# power-shield-v220.net
KiCad netlist of a schematic drawn in EAGLE
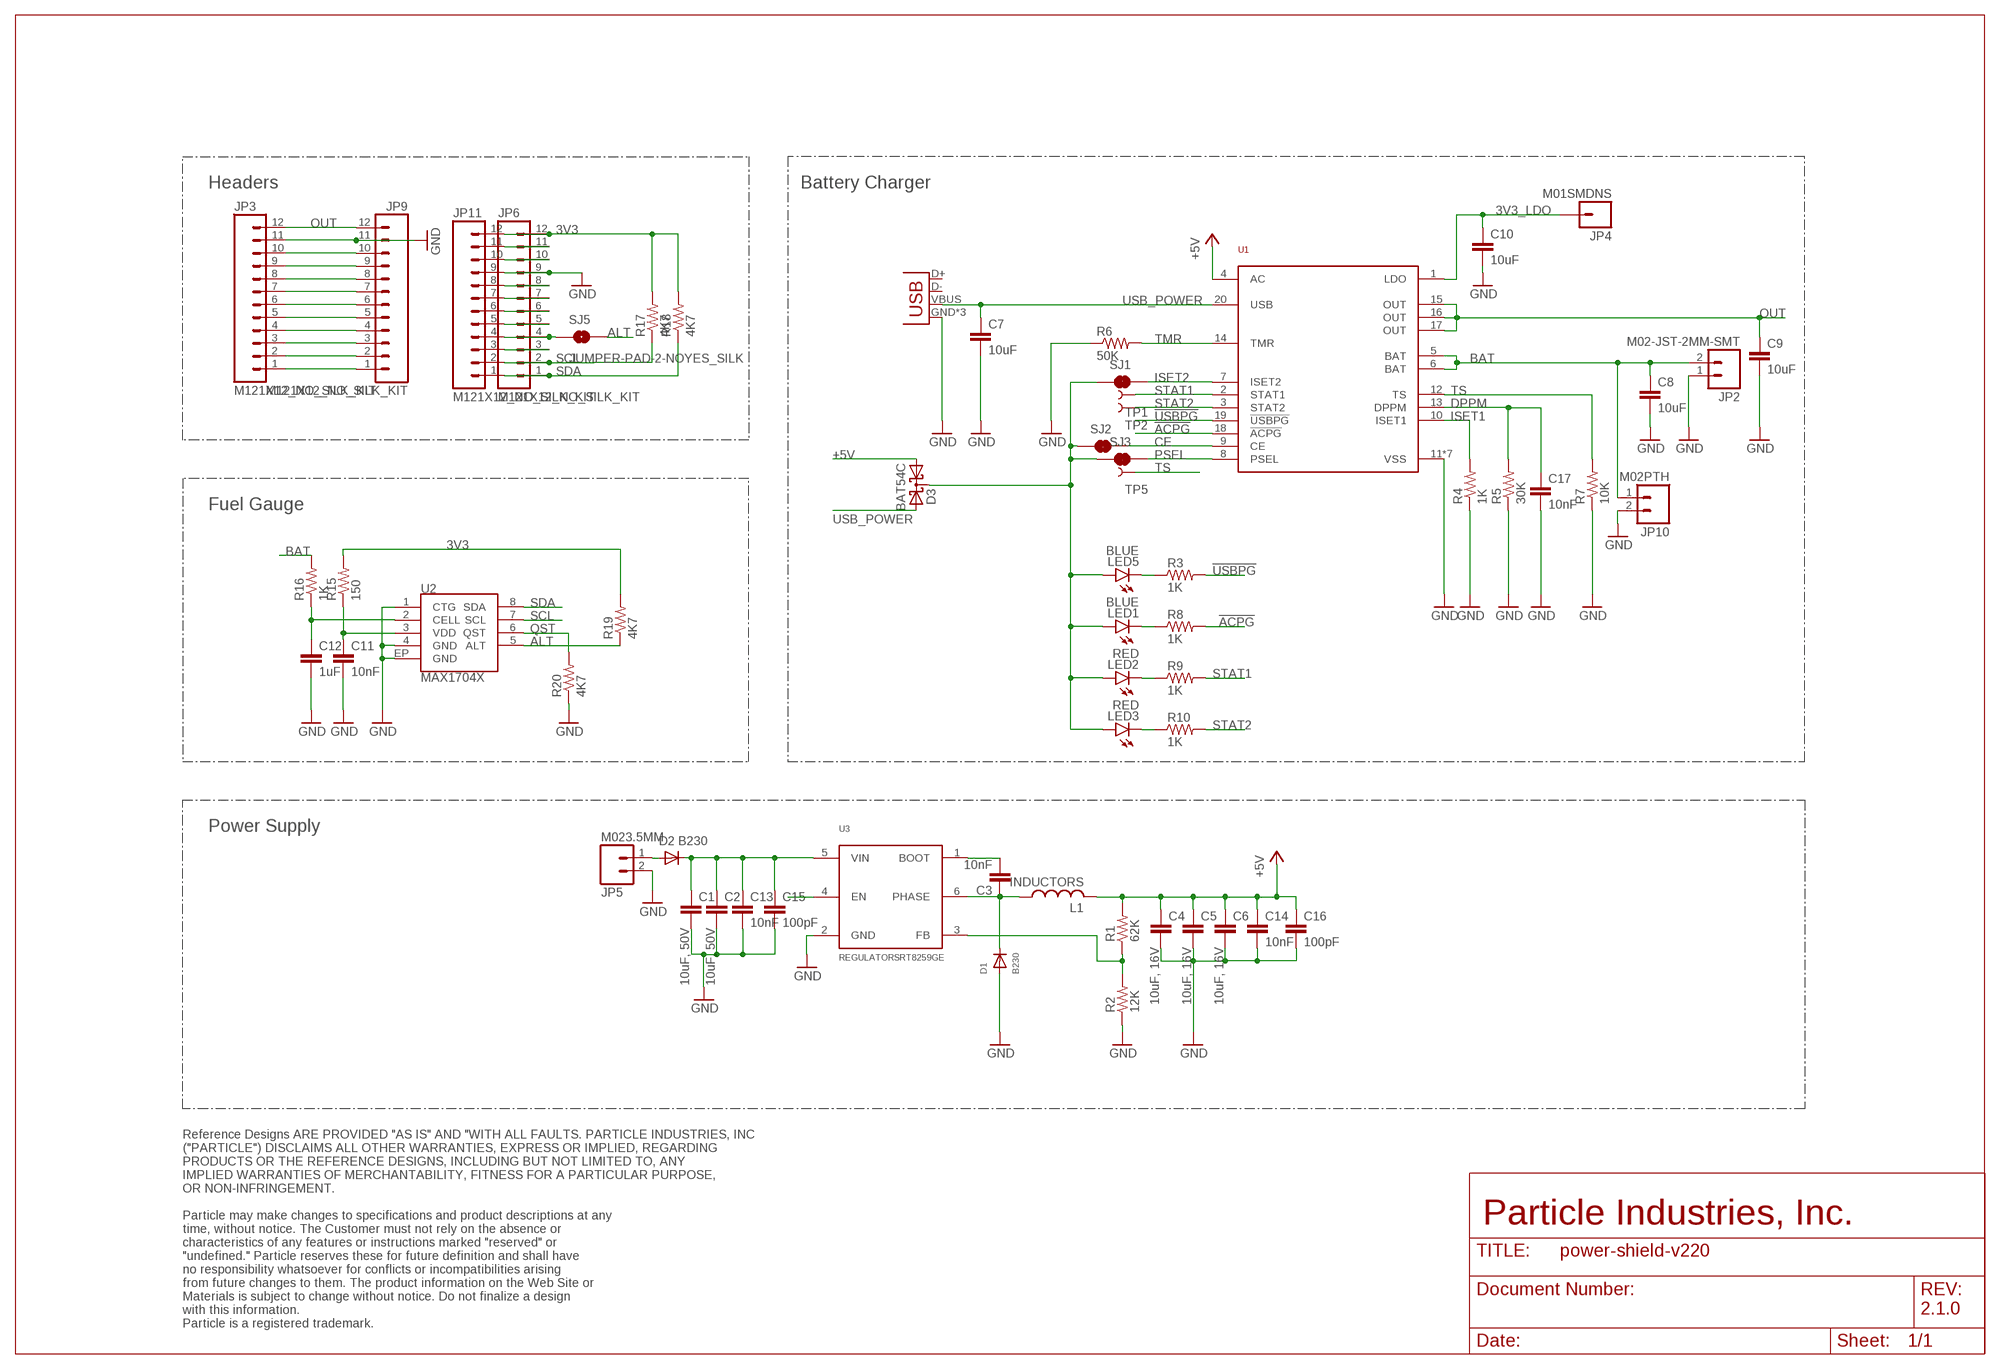
[diagram p0: schematic, sheet 1]

(export (version "E")
  (design (tool "Eeschema 10.0.6"))
  (components
    (comp (ref "C1")
      (value "10uF, 50V")
      (footprint "eagle-import:1206")
      (libsource (lib "eagle-import") (part "CAP1206"))
    )
    (comp (ref "C2")
      (value "10uF, 50V")
      (footprint "eagle-import:1206")
      (libsource (lib "eagle-import") (part "CAP1206"))
    )
    (comp (ref "C3")
      (value "10nF")
      (footprint "eagle-import:0402-CAP")
      (libsource (lib "eagle-import") (part "CAP0402-CAP"))
    )
    (comp (ref "C4")
      (value "10uF, 16V")
      (footprint "eagle-import:1206")
      (libsource (lib "eagle-import") (part "CAP1206"))
    )
    (comp (ref "C5")
      (value "10uF, 16V")
      (footprint "eagle-import:1206")
      (libsource (lib "eagle-import") (part "CAP1206"))
    )
    (comp (ref "C6")
      (value "10uF, 16V")
      (footprint "eagle-import:1206")
      (libsource (lib "eagle-import") (part "CAP1206"))
    )
    (comp (ref "C7")
      (value "10uF")
      (footprint "eagle-import:0603-CAP")
      (libsource (lib "eagle-import") (part "CAP0603-CAP"))
    )
    (comp (ref "C8")
      (value "10uF")
      (footprint "eagle-import:0603-CAP")
      (libsource (lib "eagle-import") (part "CAP0603-CAP"))
    )
    (comp (ref "C9")
      (value "10uF")
      (footprint "eagle-import:0603-CAP")
      (libsource (lib "eagle-import") (part "CAP0603-CAP"))
    )
    (comp (ref "C10")
      (value "10uF")
      (footprint "eagle-import:0603-CAP")
      (libsource (lib "eagle-import") (part "CAP0603-CAP"))
    )
    (comp (ref "C11")
      (value "10nF")
      (footprint "eagle-import:0402-CAP")
      (libsource (lib "eagle-import") (part "CAP0402-CAP"))
    )
    (comp (ref "C12")
      (value "1uF")
      (footprint "eagle-import:0402-CAP")
      (libsource (lib "eagle-import") (part "CAP0402-CAP"))
    )
    (comp (ref "C13")
      (value "10nF")
      (footprint "eagle-import:0402-CAP")
      (libsource (lib "eagle-import") (part "CAP0402-CAP"))
    )
    (comp (ref "C14")
      (value "10nF")
      (footprint "eagle-import:0402-CAP")
      (libsource (lib "eagle-import") (part "CAP0402-CAP"))
    )
    (comp (ref "C15")
      (value "100pF")
      (footprint "eagle-import:0402-CAP")
      (libsource (lib "eagle-import") (part "CAP0402-CAP"))
    )
    (comp (ref "C16")
      (value "100pF")
      (footprint "eagle-import:0402-CAP")
      (libsource (lib "eagle-import") (part "CAP0402-CAP"))
    )
    (comp (ref "C17")
      (value "10nF")
      (footprint "eagle-import:0402-CAP")
      (libsource (lib "eagle-import") (part "CAP0402-CAP"))
    )
    (comp (ref "D1")
      (value "B230")
      (footprint "eagle-import:SMADIODE")
      (libsource (lib "eagle-import") (part "DIODESMA"))
    )
    (comp (ref "D2")
      (value "B230")
      (footprint "eagle-import:SMADIODE")
      (libsource (lib "eagle-import") (part "DIODESMA"))
    )
    (comp (ref "D3")
      (value "BAT54C")
      (footprint "eagle-import:SOT23")
      (libsource (lib "eagle-import") (part "BAT54C"))
    )
    (comp (ref "JP1")
      (value "USBUSB-MICROB-SLOT-HOLE")
      (footprint "eagle-import:USB-MICROB-SLOT-HOLE")
      (libsource (lib "eagle-import") (part "USBUSB-MICROB-SLOT-HOLE"))
    )
    (comp (ref "JP2")
      (value "M02-JST-2MM-SMT")
      (footprint "eagle-import:JST-2-SMD")
      (libsource (lib "eagle-import") (part "M02-JST-2MM-SMT"))
    )
    (comp (ref "JP3")
      (value "M121X12_NO_SILK_KIT")
      (footprint "eagle-import:1X12_NO_SILK_KIT")
      (libsource (lib "eagle-import") (part "M121X12_NO_SILK_KIT"))
    )
    (comp (ref "JP4")
      (value "M01SMDNS")
      (footprint "eagle-import:1X01NS")
      (libsource (lib "eagle-import") (part "M01SMDNS"))
    )
    (comp (ref "JP5")
      (value "M023.5MM")
      (footprint "eagle-import:SCREWTERMINAL-3.5MM-2")
      (libsource (lib "eagle-import") (part "M023.5MM"))
    )
    (comp (ref "JP6")
      (value "M121X12_NO_SILK_KIT")
      (footprint "eagle-import:1X12_NO_SILK_KIT")
      (libsource (lib "eagle-import") (part "M121X12_NO_SILK_KIT"))
    )
    (comp (ref "JP9")
      (value "M121X12_NO_SILK_KIT")
      (footprint "eagle-import:1X12_NO_SILK_KIT")
      (libsource (lib "eagle-import") (part "M121X12_NO_SILK_KIT"))
    )
    (comp (ref "JP10")
      (value "M02PTH")
      (footprint "eagle-import:1X02")
      (libsource (lib "eagle-import") (part "M02PTH"))
    )
    (comp (ref "JP11")
      (value "M121X12_NO_SILK_KIT")
      (footprint "eagle-import:1X12_NO_SILK_KIT")
      (libsource (lib "eagle-import") (part "M121X12_NO_SILK_KIT"))
    )
    (comp (ref "L1")
      (value "INDUCTORS")
      (footprint "eagle-import:NR8040T6R8N")
      (libsource (lib "eagle-import") (part "INDUCTORS"))
    )
    (comp (ref "LED1")
      (value "BLUE")
      (footprint "eagle-import:LED-0603")
      (libsource (lib "eagle-import") (part "LED0603"))
    )
    (comp (ref "LED2")
      (value "RED")
      (footprint "eagle-import:LED-0603")
      (libsource (lib "eagle-import") (part "LED0603"))
    )
    (comp (ref "LED3")
      (value "RED")
      (footprint "eagle-import:LED-0603")
      (libsource (lib "eagle-import") (part "LED0603"))
    )
    (comp (ref "LED5")
      (value "BLUE")
      (footprint "eagle-import:LED-0603")
      (libsource (lib "eagle-import") (part "LED0603"))
    )
    (comp (ref "R1")
      (value "62K")
      (footprint "eagle-import:0603-RES")
      (libsource (lib "eagle-import") (part "RESISTOR0603-RES"))
    )
    (comp (ref "R2")
      (value "12K")
      (footprint "eagle-import:0603-RES")
      (libsource (lib "eagle-import") (part "RESISTOR0603-RES"))
    )
    (comp (ref "R3")
      (value "1K")
      (footprint "eagle-import:0402-RES")
      (libsource (lib "eagle-import") (part "RESISTOR0402-RES"))
    )
    (comp (ref "R4")
      (value "1K")
      (footprint "eagle-import:0402-RES")
      (libsource (lib "eagle-import") (part "RESISTOR0402-RES"))
    )
    (comp (ref "R5")
      (value "30K")
      (footprint "eagle-import:0402-RES")
      (libsource (lib "eagle-import") (part "RESISTOR0402-RES"))
    )
    (comp (ref "R6")
      (value "50K")
      (footprint "eagle-import:0402-RES")
      (libsource (lib "eagle-import") (part "RESISTOR0402-RES"))
    )
    (comp (ref "R7")
      (value "10K")
      (footprint "eagle-import:0402-RES")
      (libsource (lib "eagle-import") (part "RESISTOR0402-RES"))
    )
    (comp (ref "R8")
      (value "1K")
      (footprint "eagle-import:0402-RES")
      (libsource (lib "eagle-import") (part "RESISTOR0402-RES"))
    )
    (comp (ref "R9")
      (value "1K")
      (footprint "eagle-import:0402-RES")
      (libsource (lib "eagle-import") (part "RESISTOR0402-RES"))
    )
    (comp (ref "R10")
      (value "1K")
      (footprint "eagle-import:0402-RES")
      (libsource (lib "eagle-import") (part "RESISTOR0402-RES"))
    )
    (comp (ref "R15")
      (value "150")
      (footprint "eagle-import:0603-RES")
      (libsource (lib "eagle-import") (part "RESISTOR0603-RES"))
    )
    (comp (ref "R16")
      (value "1K")
      (footprint "eagle-import:0603-RES")
      (libsource (lib "eagle-import") (part "RESISTOR0603-RES"))
    )
    (comp (ref "R17")
      (value "4K7")
      (footprint "eagle-import:0402-RES")
      (libsource (lib "eagle-import") (part "RESISTOR0402-RES"))
    )
    (comp (ref "R18")
      (value "4K7")
      (footprint "eagle-import:0402-RES")
      (libsource (lib "eagle-import") (part "RESISTOR0402-RES"))
    )
    (comp (ref "R19")
      (value "4K7")
      (footprint "eagle-import:0402-RES")
      (libsource (lib "eagle-import") (part "RESISTOR0402-RES"))
    )
    (comp (ref "R20")
      (value "4K7")
      (footprint "eagle-import:0402-RES")
      (libsource (lib "eagle-import") (part "RESISTOR0402-RES"))
    )
    (comp (ref "SJ1")
      (value "JUMPER-PAD-2-NC_BY_TRACE")
      (footprint "eagle-import:PAD-JUMPER-2-NC_BY_TRACE_YES_SILK")
      (libsource (lib "eagle-import") (part "JUMPER-PAD-2-NC_BY_TRACE"))
    )
    (comp (ref "SJ2")
      (value "JUMPER-PAD-2-NC_BY_TRACE")
      (footprint "eagle-import:PAD-JUMPER-2-NC_BY_TRACE_YES_SILK")
      (libsource (lib "eagle-import") (part "JUMPER-PAD-2-NC_BY_TRACE"))
    )
    (comp (ref "SJ3")
      (value "JUMPER-PAD-2-NC_BY_TRACE")
      (footprint "eagle-import:PAD-JUMPER-2-NC_BY_TRACE_YES_SILK")
      (libsource (lib "eagle-import") (part "JUMPER-PAD-2-NC_BY_TRACE"))
    )
    (comp (ref "SJ5")
      (value "JUMPER-PAD-2-NOYES_SILK")
      (footprint "eagle-import:PAD-JUMPER-2-NO_YES_SILK")
      (libsource (lib "eagle-import") (part "JUMPER-PAD-2-NOYES_SILK"))
    )
    (comp (ref "TP1")
      (value "TEST-POINT3")
      (footprint "eagle-import:PAD.03X.03")
      (libsource (lib "eagle-import") (part "TEST-POINT3"))
    )
    (comp (ref "TP2")
      (value "TEST-POINT3")
      (footprint "eagle-import:PAD.03X.03")
      (libsource (lib "eagle-import") (part "TEST-POINT3"))
    )
    (comp (ref "TP5")
      (value "TEST-POINT3")
      (footprint "eagle-import:PAD.03X.03")
      (libsource (lib "eagle-import") (part "TEST-POINT3"))
    )
    (comp (ref "U1")
      (value "BQ24030BQ24030")
      (footprint "eagle-import:R-PVQFN-N20")
      (libsource (lib "eagle-import") (part "BQ24030BQ24030"))
    )
    (comp (ref "U2")
      (value "MAX1704X")
      (footprint "eagle-import:TDFN-8")
      (libsource (lib "eagle-import") (part "MAX1704X"))
    )
    (comp (ref "U3")
      (value "REGULATORSRT8259GE")
      (footprint "eagle-import:SOT23-6")
      (libsource (lib "eagle-import") (part "REGULATORSRT8259GE"))
    )
  )
  (nets
    (net (code "1") (name "+5V") (class "Default")
      (node (ref "C14") (pin "1") (pinfunction "1_1") (pintype "passive"))
      (node (ref "C16") (pin "1") (pinfunction "1_1") (pintype "passive"))
      (node (ref "C4") (pin "1") (pinfunction "1_1") (pintype "passive"))
      (node (ref "C5") (pin "1") (pinfunction "1_1") (pintype "passive"))
      (node (ref "C6") (pin "1") (pinfunction "1_1") (pintype "passive"))
      (node (ref "D3") (pin "1") (pinfunction "A1_1") (pintype "passive"))
      (node (ref "L1") (pin "P$2") (pinfunction "2_P$2") (pintype "passive"))
      (node (ref "R1") (pin "2") (pinfunction "2_2") (pintype "passive"))
      (node (ref "U1") (pin "4") (pinfunction "AC_4") (pintype "power_in"))
    )
    (net (code "2") (name "/3V3") (class "Default")
      (node (ref "JP11") (pin "12") (pinfunction "12_12") (pintype "passive"))
      (node (ref "JP6") (pin "12") (pinfunction "12_12") (pintype "passive"))
      (node (ref "R15") (pin "2") (pinfunction "2_2") (pintype "passive"))
      (node (ref "R17") (pin "2") (pinfunction "2_2") (pintype "passive"))
      (node (ref "R18") (pin "2") (pinfunction "2_2") (pintype "passive"))
      (node (ref "R19") (pin "2") (pinfunction "2_2") (pintype "passive"))
    )
    (net (code "3") (name "/3V3_LDO") (class "Default")
      (node (ref "C10") (pin "1") (pinfunction "1_1") (pintype "passive"))
      (node (ref "JP4") (pin "1") (pinfunction "1_1") (pintype "passive"))
      (node (ref "U1") (pin "1") (pinfunction "LDO_1") (pintype "output"))
    )
    (net (code "4") (name "/ALT") (class "Default")
      (node (ref "R19") (pin "1") (pinfunction "1_1") (pintype "passive"))
      (node (ref "SJ5") (pin "2") (pinfunction "2_2") (pintype "passive"))
      (node (ref "U2") (pin "5") (pinfunction "ALT_5") (pintype "bidirectional"))
    )
    (net (code "5") (name "/BAT") (class "Default")
      (node (ref "C8") (pin "1") (pinfunction "1_1") (pintype "passive"))
      (node (ref "JP10") (pin "1") (pinfunction "1_1") (pintype "passive"))
      (node (ref "JP2") (pin "2") (pinfunction "1_2") (pintype "passive"))
      (node (ref "R16") (pin "2") (pinfunction "2_2") (pintype "passive"))
      (node (ref "U1") (pin "5") (pinfunction "BAT_5") (pintype "output"))
      (node (ref "U1") (pin "6") (pinfunction "BAT_6") (pintype "output"))
    )
    (net (code "6") (name "/CE") (class "Default")
      (node (ref "SJ2") (pin "2") (pinfunction "2_2") (pintype "passive"))
      (node (ref "U1") (pin "9") (pinfunction "CE_9") (pintype "input"))
    )
    (net (code "7") (name "/DPPM") (class "Default")
      (node (ref "C17") (pin "1") (pinfunction "1_1") (pintype "passive"))
      (node (ref "R5") (pin "2") (pinfunction "2_2") (pintype "passive"))
      (node (ref "U1") (pin "13") (pinfunction "DPPM_13") (pintype "bidirectional"))
    )
    (net (code "8") (name "/ISET1") (class "Default")
      (node (ref "R4") (pin "2") (pinfunction "2_2") (pintype "passive"))
      (node (ref "U1") (pin "10") (pinfunction "ISET1_10") (pintype "bidirectional"))
    )
    (net (code "9") (name "/ISET2") (class "Default")
      (node (ref "SJ1") (pin "2") (pinfunction "2_2") (pintype "passive"))
      (node (ref "U1") (pin "7") (pinfunction "ISET2_7") (pintype "input"))
    )
    (net (code "10") (name "/OUT") (class "Default")
      (node (ref "C9") (pin "1") (pinfunction "1_1") (pintype "passive"))
      (node (ref "JP3") (pin "12") (pinfunction "12_12") (pintype "passive"))
      (node (ref "JP9") (pin "12") (pinfunction "12_12") (pintype "passive"))
      (node (ref "U1") (pin "15") (pinfunction "OUT_15") (pintype "output"))
      (node (ref "U1") (pin "16") (pinfunction "OUT_16") (pintype "output"))
      (node (ref "U1") (pin "17") (pinfunction "OUT_17") (pintype "output"))
    )
    (net (code "11") (name "/PSEL") (class "Default")
      (node (ref "SJ3") (pin "2") (pinfunction "2_2") (pintype "passive"))
      (node (ref "U1") (pin "8") (pinfunction "PSEL_8") (pintype "input"))
    )
    (net (code "12") (name "/QST") (class "Default")
      (node (ref "R20") (pin "2") (pinfunction "2_2") (pintype "passive"))
      (node (ref "U2") (pin "6") (pinfunction "QST_6") (pintype "bidirectional"))
    )
    (net (code "13") (name "/SCL") (class "Default")
      (node (ref "JP11") (pin "2") (pinfunction "2_2") (pintype "passive"))
      (node (ref "JP6") (pin "2") (pinfunction "2_2") (pintype "passive"))
      (node (ref "R17") (pin "1") (pinfunction "1_1") (pintype "passive"))
      (node (ref "U2") (pin "7") (pinfunction "SCL_7") (pintype "bidirectional"))
    )
    (net (code "14") (name "/SDA") (class "Default")
      (node (ref "JP11") (pin "1") (pinfunction "1_1") (pintype "passive"))
      (node (ref "JP6") (pin "1") (pinfunction "1_1") (pintype "passive"))
      (node (ref "R18") (pin "1") (pinfunction "1_1") (pintype "passive"))
      (node (ref "U2") (pin "8") (pinfunction "SDA_8") (pintype "bidirectional"))
    )
    (net (code "15") (name "/STAT1") (class "Default")
      (node (ref "R9") (pin "2") (pinfunction "2_2") (pintype "passive"))
      (node (ref "TP1") (pin "P$1") (pinfunction "1_P$1") (pintype "bidirectional"))
      (node (ref "U1") (pin "2") (pinfunction "STAT1_2") (pintype "output"))
    )
    (net (code "16") (name "/STAT2") (class "Default")
      (node (ref "R10") (pin "2") (pinfunction "2_2") (pintype "passive"))
      (node (ref "TP2") (pin "P$1") (pinfunction "1_P$1") (pintype "bidirectional"))
      (node (ref "U1") (pin "3") (pinfunction "STAT2_3") (pintype "output"))
    )
    (net (code "17") (name "/TMR") (class "Default")
      (node (ref "R6") (pin "2") (pinfunction "2_2") (pintype "passive"))
      (node (ref "U1") (pin "14") (pinfunction "TMR_14") (pintype "power_in"))
    )
    (net (code "18") (name "/TS") (class "Default")
      (node (ref "R7") (pin "2") (pinfunction "2_2") (pintype "passive"))
      (node (ref "TP5") (pin "P$1") (pinfunction "1_P$1") (pintype "bidirectional"))
      (node (ref "U1") (pin "12") (pinfunction "TS_12") (pintype "bidirectional"))
    )
    (net (code "19") (name "/USB_POWER") (class "Default")
      (node (ref "C7") (pin "1") (pinfunction "1_1") (pintype "passive"))
      (node (ref "D3") (pin "2") (pinfunction "A2_2") (pintype "passive"))
      (node (ref "JP1") (pin "VBUS") (pinfunction "VBUS_VBUS") (pintype "bidirectional"))
      (node (ref "U1") (pin "20") (pinfunction "USB_20") (pintype "power_in"))
    )
    (net (code "20") (name "/~{ACPG}") (class "Default")
      (node (ref "R8") (pin "2") (pinfunction "2_2") (pintype "passive"))
      (node (ref "U1") (pin "18") (pinfunction "~{ACPG}_18") (pintype "input"))
    )
    (net (code "21") (name "/~{USBPG}") (class "Default")
      (node (ref "R3") (pin "2") (pinfunction "2_2") (pintype "passive"))
      (node (ref "U1") (pin "19") (pinfunction "~{USBPG}_19") (pintype "input"))
    )
    (net (code "22") (name "GND") (class "Default")
      (node (ref "C1") (pin "2") (pinfunction "2_2") (pintype "passive"))
      (node (ref "C10") (pin "2") (pinfunction "2_2") (pintype "passive"))
      (node (ref "C11") (pin "2") (pinfunction "2_2") (pintype "passive"))
      (node (ref "C12") (pin "2") (pinfunction "2_2") (pintype "passive"))
      (node (ref "C13") (pin "2") (pinfunction "2_2") (pintype "passive"))
      (node (ref "C14") (pin "2") (pinfunction "2_2") (pintype "passive"))
      (node (ref "C15") (pin "2") (pinfunction "2_2") (pintype "passive"))
      (node (ref "C16") (pin "2") (pinfunction "2_2") (pintype "passive"))
      (node (ref "C17") (pin "2") (pinfunction "2_2") (pintype "passive"))
      (node (ref "C2") (pin "2") (pinfunction "2_2") (pintype "passive"))
      (node (ref "C4") (pin "2") (pinfunction "2_2") (pintype "passive"))
      (node (ref "C5") (pin "2") (pinfunction "2_2") (pintype "passive"))
      (node (ref "C6") (pin "2") (pinfunction "2_2") (pintype "passive"))
      (node (ref "C7") (pin "2") (pinfunction "2_2") (pintype "passive"))
      (node (ref "C8") (pin "2") (pinfunction "2_2") (pintype "passive"))
      (node (ref "C9") (pin "2") (pinfunction "2_2") (pintype "passive"))
      (node (ref "D1") (pin "A") (pinfunction "A_A") (pintype "passive"))
      (node (ref "JP1") (pin "GND") (pinfunction "GND_GND") (pintype "bidirectional"))
      (node (ref "JP1") (pin "MT1") (pinfunction "GND_MT1") (pintype "bidirectional"))
      (node (ref "JP1") (pin "MT2") (pinfunction "GND_MT2") (pintype "bidirectional"))
      (node (ref "JP10") (pin "2") (pinfunction "2_2") (pintype "passive"))
      (node (ref "JP11") (pin "9") (pinfunction "9_9") (pintype "passive"))
      (node (ref "JP2") (pin "1") (pinfunction "2_1") (pintype "passive"))
      (node (ref "JP3") (pin "11") (pinfunction "11_11") (pintype "passive"))
      (node (ref "JP5") (pin "2") (pinfunction "2_2") (pintype "passive"))
      (node (ref "JP6") (pin "9") (pinfunction "9_9") (pintype "passive"))
      (node (ref "JP9") (pin "11") (pinfunction "11_11") (pintype "passive"))
      (node (ref "R2") (pin "1") (pinfunction "1_1") (pintype "passive"))
      (node (ref "R20") (pin "1") (pinfunction "1_1") (pintype "passive"))
      (node (ref "R4") (pin "1") (pinfunction "1_1") (pintype "passive"))
      (node (ref "R5") (pin "1") (pinfunction "1_1") (pintype "passive"))
      (node (ref "R6") (pin "1") (pinfunction "1_1") (pintype "passive"))
      (node (ref "R7") (pin "1") (pinfunction "1_1") (pintype "passive"))
      (node (ref "U1") (pin "11") (pinfunction "VSS_11") (pintype "power_in"))
      (node (ref "U1") (pin "21") (pinfunction "VSS_21") (pintype "power_in"))
      (node (ref "U1") (pin "22") (pinfunction "VSS_22") (pintype "power_in"))
      (node (ref "U1") (pin "23") (pinfunction "VSS_23") (pintype "power_in"))
      (node (ref "U1") (pin "24") (pinfunction "VSS_24") (pintype "power_in"))
      (node (ref "U1") (pin "25") (pinfunction "VSS_25") (pintype "power_in"))
      (node (ref "U1") (pin "26") (pinfunction "VSS_26") (pintype "power_in"))
      (node (ref "U2") (pin "1") (pinfunction "CTG_1") (pintype "bidirectional"))
      (node (ref "U2") (pin "4") (pinfunction "GND_4") (pintype "bidirectional"))
      (node (ref "U2") (pin "EP") (pinfunction "GND_EP") (pintype "bidirectional"))
      (node (ref "U3") (pin "2") (pinfunction "GND_2") (pintype "bidirectional"))
    )
    (net (code "23") (name "Net-(D2-PadA)") (class "Default")
      (node (ref "D2") (pin "A") (pinfunction "A_A") (pintype "passive"))
      (node (ref "JP5") (pin "1") (pinfunction "1_1") (pintype "passive"))
    )
    (net (code "24") (name "Net-(D3-CC)") (class "Default")
      (node (ref "D3") (pin "3") (pinfunction "CC_3") (pintype "passive"))
      (node (ref "LED1") (pin "A") (pinfunction "A_A") (pintype "passive"))
      (node (ref "LED2") (pin "A") (pinfunction "A_A") (pintype "passive"))
      (node (ref "LED3") (pin "A") (pinfunction "A_A") (pintype "passive"))
      (node (ref "LED5") (pin "A") (pinfunction "A_A") (pintype "passive"))
      (node (ref "SJ1") (pin "1") (pinfunction "1_1") (pintype "passive"))
      (node (ref "SJ2") (pin "1") (pinfunction "1_1") (pintype "passive"))
      (node (ref "SJ3") (pin "1") (pinfunction "1_1") (pintype "passive"))
    )
    (net (code "25") (name "Net-(JP3-Pad1)") (class "Default")
      (node (ref "JP3") (pin "1") (pinfunction "1_1") (pintype "passive"))
      (node (ref "JP9") (pin "1") (pinfunction "1_1") (pintype "passive"))
    )
    (net (code "26") (name "Net-(JP3-Pad2)") (class "Default")
      (node (ref "JP3") (pin "2") (pinfunction "2_2") (pintype "passive"))
      (node (ref "JP9") (pin "2") (pinfunction "2_2") (pintype "passive"))
    )
    (net (code "27") (name "Net-(JP3-Pad3)") (class "Default")
      (node (ref "JP3") (pin "3") (pinfunction "3_3") (pintype "passive"))
      (node (ref "JP9") (pin "3") (pinfunction "3_3") (pintype "passive"))
    )
    (net (code "28") (name "Net-(JP3-Pad4)") (class "Default")
      (node (ref "JP3") (pin "4") (pinfunction "4_4") (pintype "passive"))
      (node (ref "JP9") (pin "4") (pinfunction "4_4") (pintype "passive"))
    )
    (net (code "29") (name "Net-(JP3-Pad5)") (class "Default")
      (node (ref "JP3") (pin "5") (pinfunction "5_5") (pintype "passive"))
      (node (ref "JP9") (pin "5") (pinfunction "5_5") (pintype "passive"))
    )
    (net (code "30") (name "Net-(JP3-Pad6)") (class "Default")
      (node (ref "JP3") (pin "6") (pinfunction "6_6") (pintype "passive"))
      (node (ref "JP9") (pin "6") (pinfunction "6_6") (pintype "passive"))
    )
    (net (code "31") (name "Net-(JP3-Pad7)") (class "Default")
      (node (ref "JP3") (pin "7") (pinfunction "7_7") (pintype "passive"))
      (node (ref "JP9") (pin "7") (pinfunction "7_7") (pintype "passive"))
    )
    (net (code "32") (name "Net-(JP3-Pad8)") (class "Default")
      (node (ref "JP3") (pin "8") (pinfunction "8_8") (pintype "passive"))
      (node (ref "JP9") (pin "8") (pinfunction "8_8") (pintype "passive"))
    )
    (net (code "33") (name "Net-(JP3-Pad9)") (class "Default")
      (node (ref "JP3") (pin "9") (pinfunction "9_9") (pintype "passive"))
      (node (ref "JP9") (pin "9") (pinfunction "9_9") (pintype "passive"))
    )
    (net (code "34") (name "Net-(JP3-Pad10)") (class "Default")
      (node (ref "JP3") (pin "10") (pinfunction "10_10") (pintype "passive"))
      (node (ref "JP9") (pin "10") (pinfunction "10_10") (pintype "passive"))
    )
    (net (code "35") (name "Net-(JP11-Pad3)") (class "Default")
      (node (ref "JP11") (pin "3") (pinfunction "3_3") (pintype "passive"))
      (node (ref "JP6") (pin "3") (pinfunction "3_3") (pintype "passive"))
    )
    (net (code "36") (name "Net-(JP11-Pad4)") (class "Default")
      (node (ref "JP11") (pin "4") (pinfunction "4_4") (pintype "passive"))
      (node (ref "JP6") (pin "4") (pinfunction "4_4") (pintype "passive"))
      (node (ref "SJ5") (pin "1") (pinfunction "1_1") (pintype "passive"))
    )
    (net (code "37") (name "Net-(JP11-Pad5)") (class "Default")
      (node (ref "JP11") (pin "5") (pinfunction "5_5") (pintype "passive"))
      (node (ref "JP6") (pin "5") (pinfunction "5_5") (pintype "passive"))
    )
    (net (code "38") (name "Net-(JP11-Pad6)") (class "Default")
      (node (ref "JP11") (pin "6") (pinfunction "6_6") (pintype "passive"))
      (node (ref "JP6") (pin "6") (pinfunction "6_6") (pintype "passive"))
    )
    (net (code "39") (name "Net-(JP11-Pad7)") (class "Default")
      (node (ref "JP11") (pin "7") (pinfunction "7_7") (pintype "passive"))
      (node (ref "JP6") (pin "7") (pinfunction "7_7") (pintype "passive"))
    )
    (net (code "40") (name "Net-(JP11-Pad8)") (class "Default")
      (node (ref "JP11") (pin "8") (pinfunction "8_8") (pintype "passive"))
      (node (ref "JP6") (pin "8") (pinfunction "8_8") (pintype "passive"))
    )
    (net (code "41") (name "Net-(JP11-Pad10)") (class "Default")
      (node (ref "JP11") (pin "10") (pinfunction "10_10") (pintype "passive"))
      (node (ref "JP6") (pin "10") (pinfunction "10_10") (pintype "passive"))
    )
    (net (code "42") (name "Net-(JP11-Pad11)") (class "Default")
      (node (ref "JP11") (pin "11") (pinfunction "11_11") (pintype "passive"))
      (node (ref "JP6") (pin "11") (pinfunction "11_11") (pintype "passive"))
    )
    (net (code "43") (name "Net-(L1-1)") (class "Default")
      (node (ref "C3") (pin "1") (pinfunction "1_1") (pintype "passive"))
      (node (ref "D1") (pin "C") (pinfunction "C_C") (pintype "passive"))
      (node (ref "L1") (pin "P$1") (pinfunction "1_P$1") (pintype "passive"))
      (node (ref "U3") (pin "6") (pinfunction "PHASE_6") (pintype "output"))
    )
    (net (code "44") (name "Net-(LED1-PadC)") (class "Default")
      (node (ref "LED1") (pin "C") (pinfunction "C_C") (pintype "passive"))
      (node (ref "R8") (pin "1") (pinfunction "1_1") (pintype "passive"))
    )
    (net (code "45") (name "Net-(LED2-PadC)") (class "Default")
      (node (ref "LED2") (pin "C") (pinfunction "C_C") (pintype "passive"))
      (node (ref "R9") (pin "1") (pinfunction "1_1") (pintype "passive"))
    )
    (net (code "46") (name "Net-(LED3-PadC)") (class "Default")
      (node (ref "LED3") (pin "C") (pinfunction "C_C") (pintype "passive"))
      (node (ref "R10") (pin "1") (pinfunction "1_1") (pintype "passive"))
    )
    (net (code "47") (name "Net-(LED5-PadC)") (class "Default")
      (node (ref "LED5") (pin "C") (pinfunction "C_C") (pintype "passive"))
      (node (ref "R3") (pin "1") (pinfunction "1_1") (pintype "passive"))
    )
    (net (code "48") (name "Net-(U2-CELL)") (class "Default")
      (node (ref "C12") (pin "1") (pinfunction "1_1") (pintype "passive"))
      (node (ref "R16") (pin "1") (pinfunction "1_1") (pintype "passive"))
      (node (ref "U2") (pin "2") (pinfunction "CELL_2") (pintype "bidirectional"))
    )
    (net (code "49") (name "Net-(U2-VDD)") (class "Default")
      (node (ref "C11") (pin "1") (pinfunction "1_1") (pintype "passive"))
      (node (ref "R15") (pin "1") (pinfunction "1_1") (pintype "passive"))
      (node (ref "U2") (pin "3") (pinfunction "VDD_3") (pintype "bidirectional"))
    )
    (net (code "50") (name "Net-(U3-BOOT)") (class "Default")
      (node (ref "C3") (pin "2") (pinfunction "2_2") (pintype "passive"))
      (node (ref "U3") (pin "1") (pinfunction "BOOT_1") (pintype "power_in"))
    )
    (net (code "51") (name "Net-(U3-FB)") (class "Default")
      (node (ref "R1") (pin "1") (pinfunction "1_1") (pintype "passive"))
      (node (ref "R2") (pin "2") (pinfunction "2_2") (pintype "passive"))
      (node (ref "U3") (pin "3") (pinfunction "FB_3") (pintype "input"))
    )
    (net (code "52") (name "Net-(U3-VIN)") (class "Default")
      (node (ref "C1") (pin "1") (pinfunction "1_1") (pintype "passive"))
      (node (ref "C13") (pin "1") (pinfunction "1_1") (pintype "passive"))
      (node (ref "C15") (pin "1") (pinfunction "1_1") (pintype "passive"))
      (node (ref "C2") (pin "1") (pinfunction "1_1") (pintype "passive"))
      (node (ref "D2") (pin "C") (pinfunction "C_C") (pintype "passive"))
      (node (ref "U3") (pin "5") (pinfunction "VIN_5") (pintype "power_in"))
    )
    (net (code "53") (name "unconnected-(JP1-PadD+)") (class "Default")
      (node (ref "JP1") (pin "D+") (pinfunction "D+_D+") (pintype "bidirectional"))
    )
    (net (code "54") (name "unconnected-(JP1-PadD-)") (class "Default")
      (node (ref "JP1") (pin "D-") (pinfunction "D-_D-") (pintype "bidirectional"))
    )
    (net (code "55") (name "unconnected-(U3-EN-Pad4)") (class "Default")
      (node (ref "U3") (pin "4") (pinfunction "EN_4") (pintype "input"))
    )
  )
)
